# TSL2561_v10.net
KiCad netlist of a schematic drawn in EAGLE
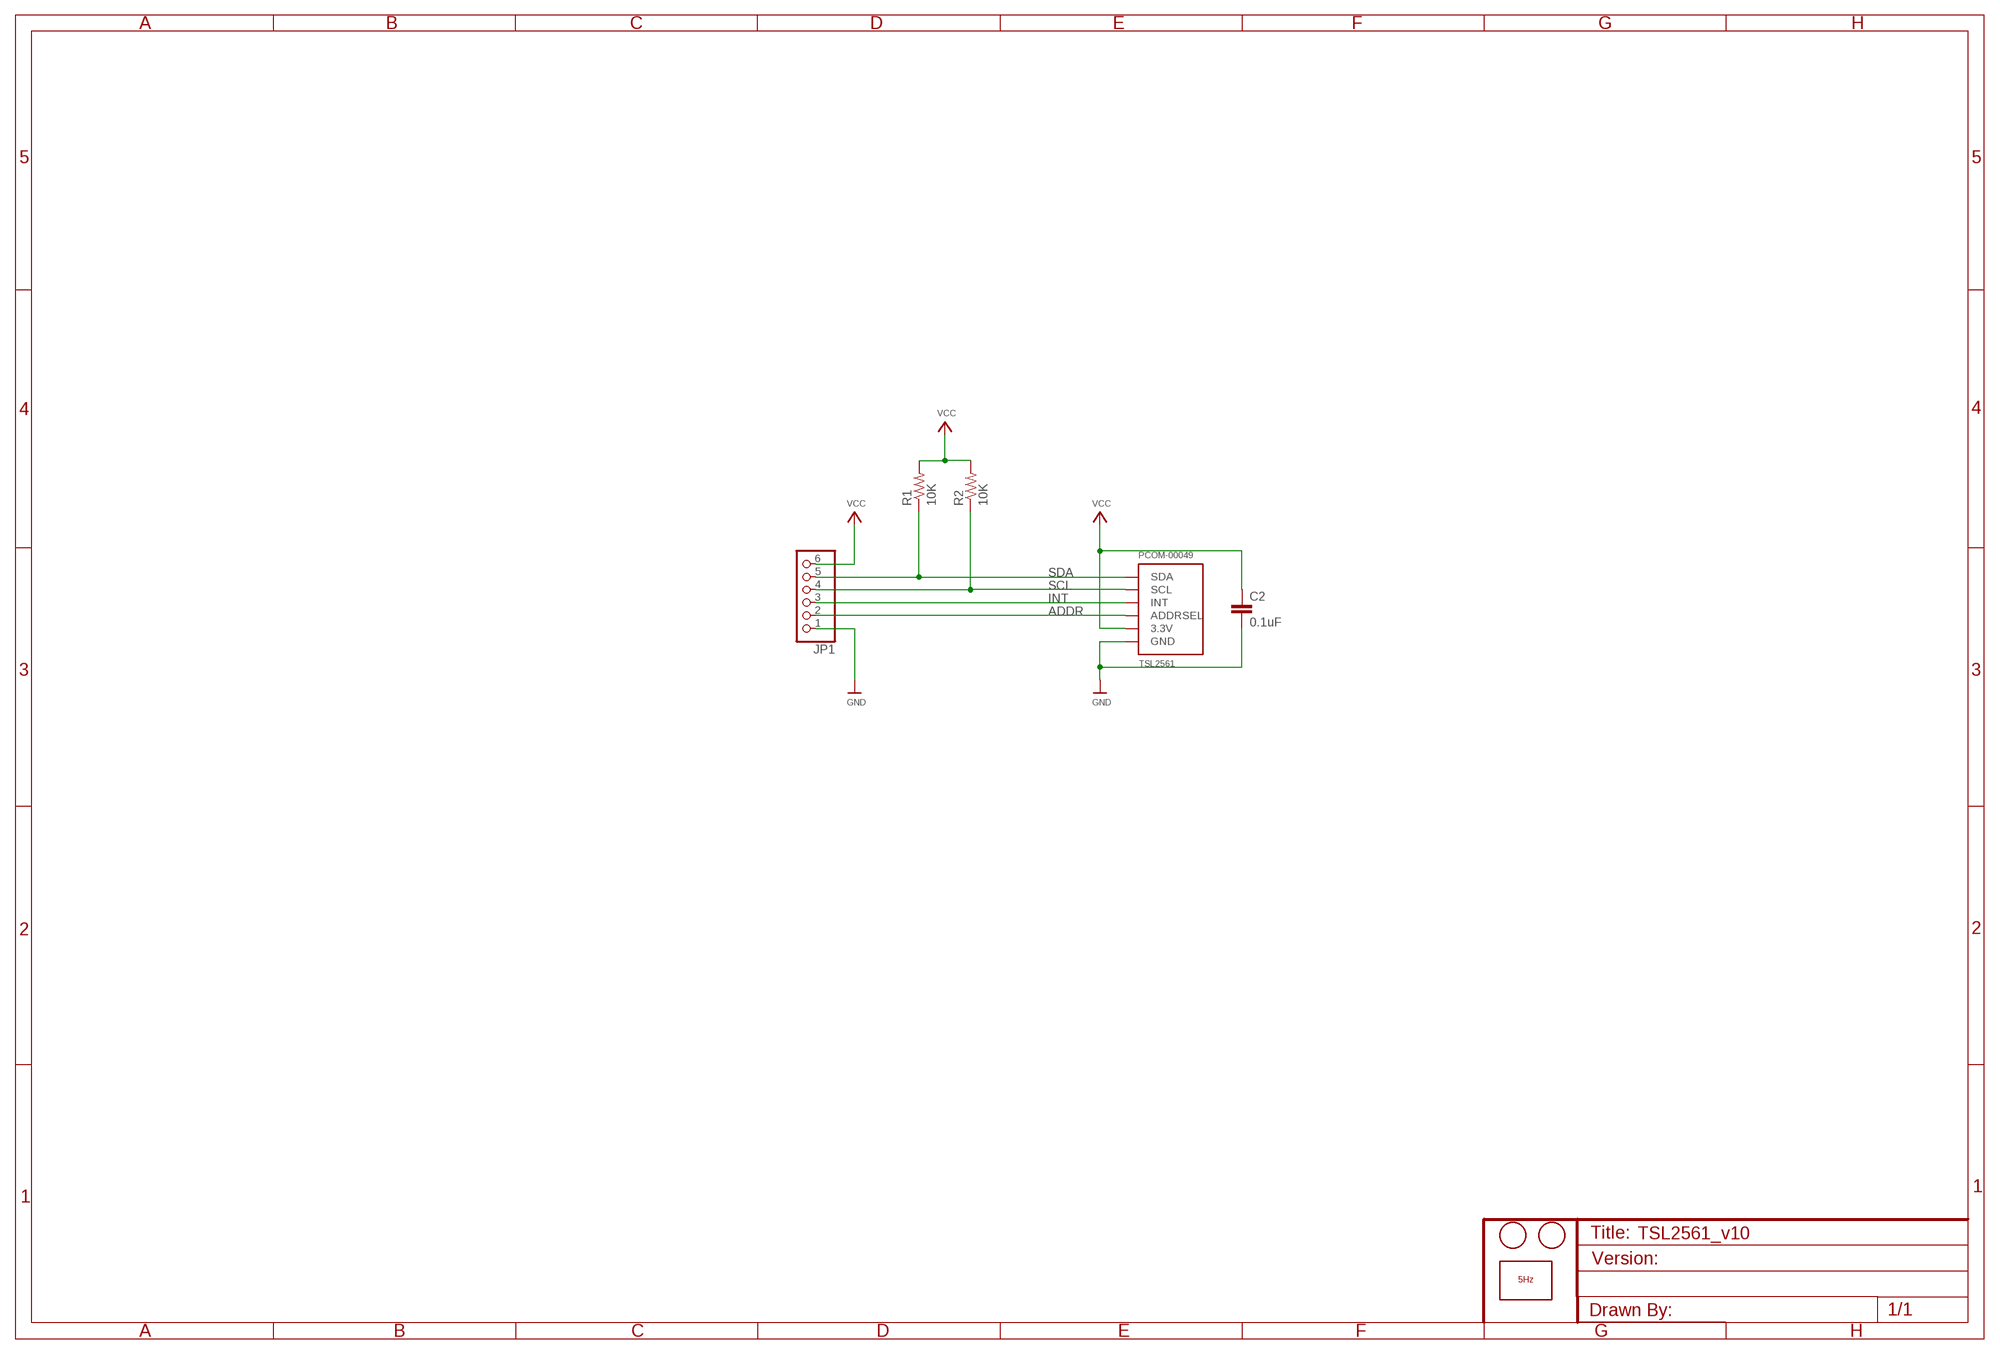
[diagram p0: schematic, sheet 1]

(export (version "E")
  (design (tool "Eeschema 10.0.6"))
  (components
    (comp (ref "C2")
      (value "0.1uF")
      (footprint "eagle-import:0603-CAP")
      (libsource (lib "eagle-import") (part "CAP0603-CAP"))
    )
    (comp (ref "JP1")
      (value "HEADER-1X676MIL")
      (footprint "eagle-import:1X06_ROUND_76")
      (libsource (lib "eagle-import") (part "HEADER-1X676MIL"))
    )
    (comp (ref "LOGO1")
      (value "LOGO_5HZ_MAIN_10MM")
      (footprint "eagle-import:5HZ_LOGO_MAIN_10MM")
      (libsource (lib "eagle-import") (part "LOGO_5HZ_MAIN_10MM"))
    )
    (comp (ref "PCOM-00049")
      (value "TSL2561")
      (footprint "eagle-import:TSL2561_FN")
      (libsource (lib "eagle-import") (part "TSL2561"))
    )
    (comp (ref "R1")
      (value "10K")
      (footprint "eagle-import:0603-RES")
      (libsource (lib "eagle-import") (part "RESISTOR0603-RES"))
    )
    (comp (ref "R2")
      (value "10K")
      (footprint "eagle-import:0603-RES")
      (libsource (lib "eagle-import") (part "RESISTOR0603-RES"))
    )
    (comp (ref "U$5")
      (value "MOUNTINGHOLE2.0")
      (footprint "eagle-import:MOUNTINGHOLE_2.0_PLATED")
      (libsource (lib "eagle-import") (part "MOUNTINGHOLE2.0"))
    )
    (comp (ref "U$6")
      (value "MOUNTINGHOLE2.0")
      (footprint "eagle-import:MOUNTINGHOLE_2.0_PLATED")
      (libsource (lib "eagle-import") (part "MOUNTINGHOLE2.0"))
    )
  )
  (nets
    (net (code "1") (name "/ADDR") (class "Default")
      (node (ref "JP1") (pin "2") (pinfunction "2_2") (pintype "passive"))
      (node (ref "PCOM-00049") (pin "ADR") (pinfunction "ADDRSEL_ADR") (pintype "bidirectional"))
    )
    (net (code "2") (name "/INT") (class "Default")
      (node (ref "JP1") (pin "3") (pinfunction "3_3") (pintype "passive"))
      (node (ref "PCOM-00049") (pin "INT") (pinfunction "INT_INT") (pintype "bidirectional"))
    )
    (net (code "3") (name "/SCL") (class "Default")
      (node (ref "JP1") (pin "4") (pinfunction "4_4") (pintype "passive"))
      (node (ref "PCOM-00049") (pin "CLK") (pinfunction "SCL_CLK") (pintype "bidirectional"))
      (node (ref "R2") (pin "1") (pinfunction "1_1") (pintype "passive"))
    )
    (net (code "4") (name "/SDA") (class "Default")
      (node (ref "JP1") (pin "5") (pinfunction "5_5") (pintype "passive"))
      (node (ref "PCOM-00049") (pin "DATA") (pinfunction "SDA_DATA") (pintype "bidirectional"))
      (node (ref "R1") (pin "1") (pinfunction "1_1") (pintype "passive"))
    )
    (net (code "5") (name "GND") (class "Default")
      (node (ref "C2") (pin "2") (pinfunction "2_2") (pintype "passive"))
      (node (ref "JP1") (pin "1") (pinfunction "1_1") (pintype "passive"))
      (node (ref "PCOM-00049") (pin "VSS") (pinfunction "GND_VSS") (pintype "bidirectional"))
    )
    (net (code "6") (name "VCC") (class "Default")
      (node (ref "C2") (pin "1") (pinfunction "1_1") (pintype "passive"))
      (node (ref "JP1") (pin "6") (pinfunction "6_6") (pintype "passive"))
      (node (ref "PCOM-00049") (pin "VDD") (pinfunction "3.3V_VDD") (pintype "bidirectional"))
      (node (ref "R1") (pin "2") (pinfunction "2_2") (pintype "passive"))
      (node (ref "R2") (pin "2") (pinfunction "2_2") (pintype "passive"))
    )
  )
)
